# rx_1280.net
KiCad netlist of a schematic drawn in EAGLE
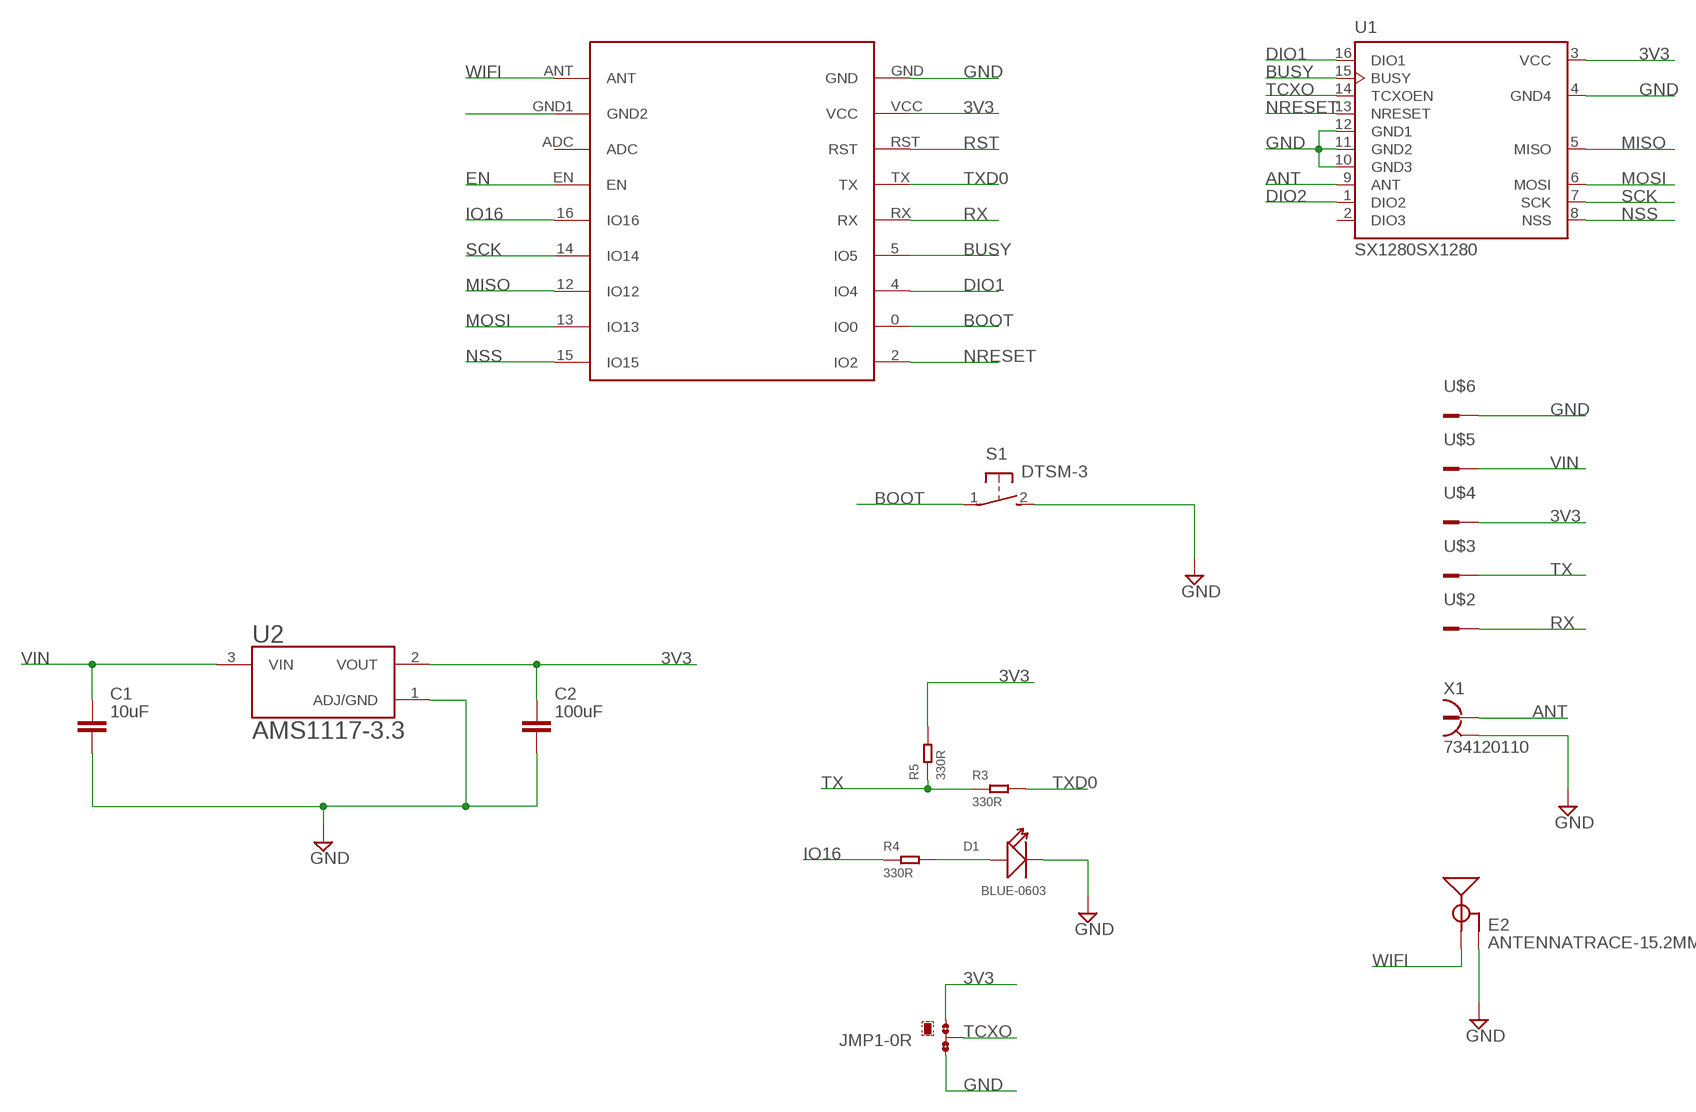
[diagram p0: schematic, sheet 1]

(export (version "E")
  (design (tool "Eeschema 10.0.6"))
  (components
    (comp (ref "C1")
      (value "10uF")
      (footprint "eagle-import:CAPM3528X210")
      (libsource (lib "eagle-import") (part "CTANTALUM-1411(3528-METRIC)_"))
    )
    (comp (ref "C2")
      (value "100uF")
      (footprint "eagle-import:CAPM3528X210")
      (libsource (lib "eagle-import") (part "CTANTALUM-1411(3528-METRIC)_"))
    )
    (comp (ref "D1")
      (value "BLUE-0603")
      (footprint "eagle-import:LED-0603")
      (fields (field (name "MPN") "19-217-BHC-ZL1M2RY-3T"))
      (libsource (lib "eagle-import") (part "SMD-LED-CLEAR-BLUE(0603)"))
    )
    (comp (ref "E2")
      (value "ANTENNATRACE-15.2MM")
      (footprint "eagle-import:TRACE_ANTENNA_2.4GHZ_15.2MM")
      (libsource (lib "eagle-import") (part "ANTENNATRACE-15.2MM"))
    )
    (comp (ref "JMP1")
      (value "0R-JUMPA")
      (footprint "eagle-import:A0R-JMP")
      (libsource (lib "eagle-import") (part "0R-JUMPA"))
    )
    (comp (ref "R3")
      (value "330R")
      (footprint "eagle-import:R0805")
      (fields (field (name "MPN") "RC0805JR-071KL"))
      (libsource (lib "eagle-import") (part "SMD-RES-330R-5%-1/8W(0805)"))
    )
    (comp (ref "R4")
      (value "330R")
      (footprint "eagle-import:R0805")
      (fields (field (name "MPN") "RC0805JR-071KL"))
      (libsource (lib "eagle-import") (part "SMD-RES-330R-5%-1/8W(0805)"))
    )
    (comp (ref "R5")
      (value "330R")
      (footprint "eagle-import:R0805")
      (fields (field (name "MPN") "RC0805JR-071KL"))
      (libsource (lib "eagle-import") (part "SMD-RES-330R-5%-1/8W(0805)"))
    )
    (comp (ref "S1")
      (value "DTSM-3")
      (footprint "eagle-import:DTSM-3")
      (libsource (lib "eagle-import") (part "DTSM-3"))
    )
    (comp (ref "U$1")
      (value "ESP-M2")
      (footprint "eagle-import:ESP-M2")
      (fields
        (field (name "MF") "Doctors of Intelligence & Technology Co., LTD")
        (field (name "MP") " ESP-M2 ")
      )
      (libsource (lib "eagle-import") (part "ESP-M2"))
    )
    (comp (ref "U$2")
      (value "CONN-1")
      (footprint "eagle-import:PAD1")
      (libsource (lib "eagle-import") (part "CONN-1"))
    )
    (comp (ref "U$3")
      (value "CONN-1")
      (footprint "eagle-import:PAD1")
      (libsource (lib "eagle-import") (part "CONN-1"))
    )
    (comp (ref "U$4")
      (value "CONN-1")
      (footprint "eagle-import:PAD1")
      (libsource (lib "eagle-import") (part "CONN-1"))
    )
    (comp (ref "U$5")
      (value "CONN-1")
      (footprint "eagle-import:PAD1")
      (libsource (lib "eagle-import") (part "CONN-1"))
    )
    (comp (ref "U$6")
      (value "CONN-1")
      (footprint "eagle-import:PAD1")
      (libsource (lib "eagle-import") (part "CONN-1"))
    )
    (comp (ref "U1")
      (value "SX1280SX1280")
      (footprint "eagle-import:SX1280")
      (libsource (lib "eagle-import") (part "SX1280SX1280"))
    )
    (comp (ref "U2")
      (value "AMS1117-3.3")
      (footprint "eagle-import:SOT229P700X180-4N")
      (fields (field (name "MF") "Advanced Monolithic Systems"))
      (libsource (lib "eagle-import") (part "AMS1117-3.3"))
    )
    (comp (ref "X1")
      (value "734120110")
      (footprint "eagle-import:734120110")
      (fields (field (name "MF") "Molex") (field (name "MP") "734-12-0110"))
      (libsource (lib "eagle-import") (part "734120110"))
    )
  )
  (nets
    (net (code "1") (name "/3V3") (class "Default")
      (node (ref "C2") (pin "1") (pinfunction "1_1") (pintype "passive"))
      (node (ref "JMP1") (pin "1") (pinfunction "1_1") (pintype "passive"))
      (node (ref "R5") (pin "2") (pinfunction "2_2") (pintype "passive"))
      (node (ref "U$1") (pin "VCC") (pinfunction "VCC_VCC") (pintype "bidirectional"))
      (node (ref "U$4") (pin "P$1") (pinfunction "1_P$1") (pintype "passive"))
      (node (ref "U1") (pin "3") (pinfunction "VCC_3") (pintype "power_in"))
      (node (ref "U2") (pin "2") (pinfunction "VOUT_2") (pintype "output"))
    )
    (net (code "2") (name "/ANT") (class "Default")
      (node (ref "U1") (pin "9") (pinfunction "ANT_9") (pintype "bidirectional"))
      (node (ref "X1") (pin "1") (pinfunction "1_1") (pintype "passive"))
    )
    (net (code "3") (name "/BOOT") (class "Default")
      (node (ref "S1") (pin "1") (pinfunction "1_1") (pintype "passive"))
      (node (ref "U$1") (pin "0") (pinfunction "IO0_0") (pintype "bidirectional"))
    )
    (net (code "4") (name "/BUSY") (class "Default")
      (node (ref "U$1") (pin "5") (pinfunction "IO5_5") (pintype "bidirectional"))
      (node (ref "U1") (pin "15") (pinfunction "BUSY_15") (pintype "input"))
    )
    (net (code "5") (name "/DIO1") (class "Default")
      (node (ref "U$1") (pin "4") (pinfunction "IO4_4") (pintype "bidirectional"))
      (node (ref "U1") (pin "16") (pinfunction "DIO1_16") (pintype "input"))
    )
    (net (code "6") (name "/DIO2") (class "Default")
      (node (ref "U1") (pin "1") (pinfunction "DIO2_1") (pintype "bidirectional"))
    )
    (net (code "7") (name "/EN") (class "Default")
      (node (ref "U$1") (pin "EN") (pinfunction "EN_EN") (pintype "bidirectional"))
    )
    (net (code "8") (name "/IO16") (class "Default")
      (node (ref "R4") (pin "1") (pinfunction "1_1") (pintype "passive"))
      (node (ref "U$1") (pin "16") (pinfunction "IO16_16") (pintype "bidirectional"))
    )
    (net (code "9") (name "/MISO") (class "Default")
      (node (ref "U$1") (pin "12") (pinfunction "IO12_12") (pintype "bidirectional"))
      (node (ref "U1") (pin "5") (pinfunction "MISO_5") (pintype "bidirectional"))
    )
    (net (code "10") (name "/MOSI") (class "Default")
      (node (ref "U$1") (pin "13") (pinfunction "IO13_13") (pintype "bidirectional"))
      (node (ref "U1") (pin "6") (pinfunction "MOSI_6") (pintype "bidirectional"))
    )
    (net (code "11") (name "/NRESET") (class "Default")
      (node (ref "U$1") (pin "2") (pinfunction "IO2_2") (pintype "bidirectional"))
      (node (ref "U1") (pin "13") (pinfunction "NRESET_13") (pintype "bidirectional"))
    )
    (net (code "12") (name "/NSS") (class "Default")
      (node (ref "U$1") (pin "15") (pinfunction "IO15_15") (pintype "bidirectional"))
      (node (ref "U1") (pin "8") (pinfunction "NSS_8") (pintype "bidirectional"))
    )
    (net (code "13") (name "/RST") (class "Default")
      (node (ref "U$1") (pin "RST") (pinfunction "RST_RST") (pintype "bidirectional"))
    )
    (net (code "14") (name "/RX") (class "Default")
      (node (ref "U$1") (pin "RX") (pinfunction "RX_RX") (pintype "bidirectional"))
      (node (ref "U$2") (pin "P$1") (pinfunction "1_P$1") (pintype "passive"))
    )
    (net (code "15") (name "/SCK") (class "Default")
      (node (ref "U$1") (pin "14") (pinfunction "IO14_14") (pintype "bidirectional"))
      (node (ref "U1") (pin "7") (pinfunction "SCK_7") (pintype "bidirectional"))
    )
    (net (code "16") (name "/TCXO") (class "Default")
      (node (ref "JMP1") (pin "2") (pinfunction "2_2") (pintype "passive"))
      (node (ref "U1") (pin "14") (pinfunction "TCXOEN_14") (pintype "input"))
    )
    (net (code "17") (name "/TX") (class "Default")
      (node (ref "R3") (pin "1") (pinfunction "1_1") (pintype "passive"))
      (node (ref "R5") (pin "1") (pinfunction "1_1") (pintype "passive"))
      (node (ref "U$3") (pin "P$1") (pinfunction "1_P$1") (pintype "passive"))
    )
    (net (code "18") (name "/TXD0") (class "Default")
      (node (ref "R3") (pin "2") (pinfunction "2_2") (pintype "passive"))
      (node (ref "U$1") (pin "TX") (pinfunction "TX_TX") (pintype "bidirectional"))
    )
    (net (code "19") (name "/VIN") (class "Default")
      (node (ref "C1") (pin "1") (pinfunction "1_1") (pintype "passive"))
      (node (ref "U$5") (pin "P$1") (pinfunction "1_P$1") (pintype "passive"))
      (node (ref "U2") (pin "3") (pinfunction "VIN_3") (pintype "input"))
    )
    (net (code "20") (name "/WIFI") (class "Default")
      (node (ref "E2") (pin "ANT") (pinfunction "SIGNAL_ANT") (pintype "bidirectional"))
      (node (ref "U$1") (pin "ANT") (pinfunction "ANT_ANT") (pintype "bidirectional"))
    )
    (net (code "21") (name "GND") (class "Default")
      (node (ref "C1") (pin "2") (pinfunction "2_2") (pintype "passive"))
      (node (ref "C2") (pin "2") (pinfunction "2_2") (pintype "passive"))
      (node (ref "D1") (pin "-") (pinfunction "-_-") (pintype "passive"))
      (node (ref "E2") (pin "GND") (pinfunction "GND_GND") (pintype "bidirectional"))
      (node (ref "JMP1") (pin "3") (pinfunction "3_3") (pintype "passive"))
      (node (ref "S1") (pin "2") (pinfunction "2_2") (pintype "passive"))
      (node (ref "U$1") (pin "GND") (pinfunction "GND_GND") (pintype "bidirectional"))
      (node (ref "U$1") (pin "GND1") (pinfunction "GND2_GND1") (pintype "bidirectional"))
      (node (ref "U$6") (pin "P$1") (pinfunction "1_P$1") (pintype "passive"))
      (node (ref "U1") (pin "10") (pinfunction "GND3_10") (pintype "power_in"))
      (node (ref "U1") (pin "11") (pinfunction "GND2_11") (pintype "power_in"))
      (node (ref "U1") (pin "12") (pinfunction "GND1_12") (pintype "power_in"))
      (node (ref "U1") (pin "4") (pinfunction "GND4_4") (pintype "power_in"))
      (node (ref "U2") (pin "1") (pinfunction "ADJ/GND_1") (pintype "power_in"))
      (node (ref "X1") (pin "S@1") (pinfunction "2_S@1") (pintype "passive"))
      (node (ref "X1") (pin "S@2") (pinfunction "2_S@2") (pintype "passive"))
      (node (ref "X1") (pin "S@3") (pinfunction "2_S@3") (pintype "passive"))
    )
    (net (code "22") (name "Net-(D1-Pad+)") (class "Default")
      (node (ref "D1") (pin "+") (pinfunction "+_+") (pintype "passive"))
      (node (ref "R4") (pin "2") (pinfunction "2_2") (pintype "passive"))
    )
    (net (code "23") (name "unconnected-(U$1-PadADC)") (class "Default")
      (node (ref "U$1") (pin "ADC") (pinfunction "ADC_ADC") (pintype "bidirectional"))
    )
    (net (code "24") (name "unconnected-(U1-DIO3-Pad2)") (class "Default")
      (node (ref "U1") (pin "2") (pinfunction "DIO3_2") (pintype "bidirectional"))
    )
  )
)
